# Voltage_Regulators.net
KiCad netlist of a schematic drawn in Altium Designer
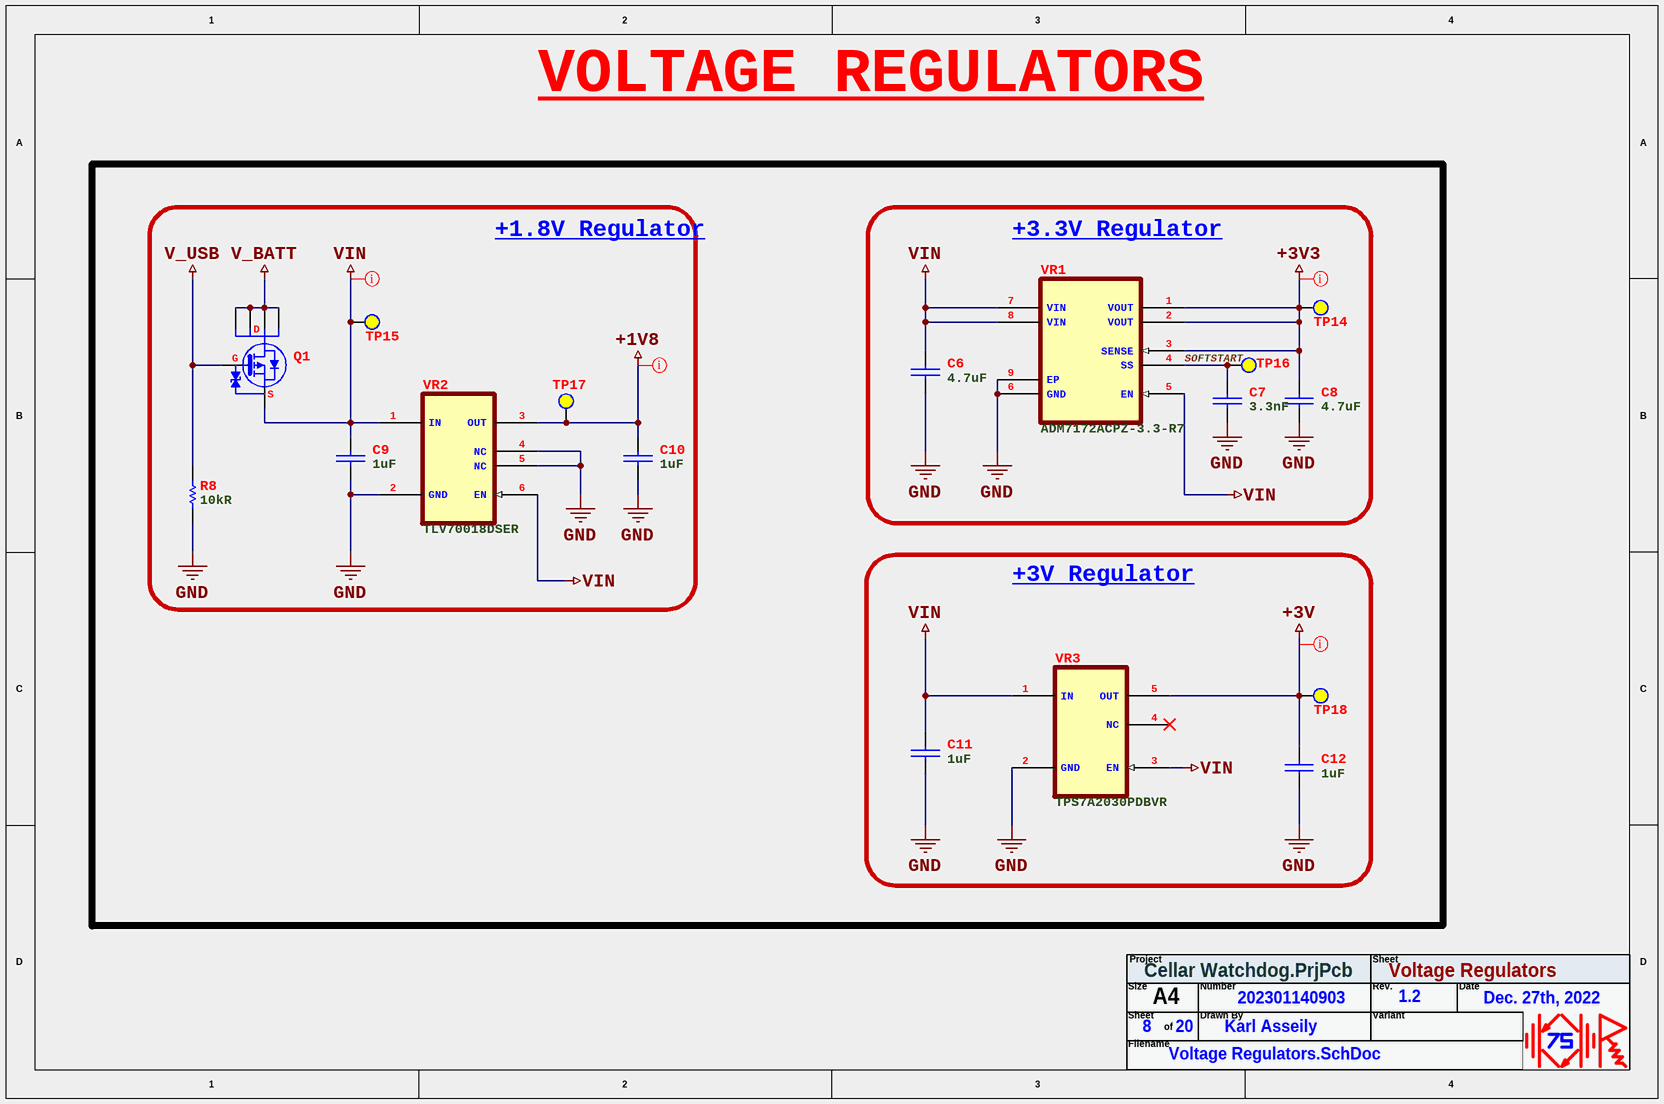
[diagram p0: Voltage Regulators.SchDoc]

(export (version "E")
  (design (tool "Eeschema 10.0.6"))
  (components
    (comp (ref "C6")
      (value "4.7uF")
      (footprint "CAP_0805")
      (description "4.7 µF ±10% 25V Ceramic Capacitor X7R 0805 (2012 Metric)")
      (fields
        (field (name "MANUFACTURER") "Yageo")
        (field (name "MANUFACTURER PART NUMBER") "CC0805KKX7R8BB475")
      )
      (libsource (lib "Cellar Watchdog") (part "CAP_4.7uF-25V-10%_0805"))
    )
    (comp (ref "C7")
      (value "3.3nF")
      (footprint "CAP_0603")
      (description "3300 pF ±10% 50V Ceramic Capacitor X7R 0603 (1608 Metric)")
      (fields
        (field (name "MANUFACTURER") "Yageo")
        (field (name "MANUFACTURER PART NUMBER") "CC0603KRX7R9BB332")
      )
      (libsource (lib "Cellar Watchdog") (part "CAP_3.3nF-50V-10%_0603"))
    )
    (comp (ref "C8")
      (value "4.7uF")
      (footprint "CAP_0805")
      (description "4.7 µF ±10% 25V Ceramic Capacitor X7R 0805 (2012 Metric)")
      (fields
        (field (name "MANUFACTURER") "Yageo")
        (field (name "MANUFACTURER PART NUMBER") "CC0805KKX7R8BB475")
      )
      (libsource (lib "Cellar Watchdog") (part "CAP_4.7uF-25V-10%_0805"))
    )
    (comp (ref "C9")
      (value "1uF")
      (footprint "CAP_0805")
      (description "1 µF ±10% 16V Ceramic Capacitor X7R 0603 (1608 Metric)")
      (fields
        (field (name "MANUFACTURER") "Yageo")
        (field (name "MANUFACTURER PART NUMBER") "CC0603KRX7R7BB105")
      )
      (libsource (lib "Cellar Watchdog") (part "CAP_1uF-16V-10%_0603"))
    )
    (comp (ref "C10")
      (value "1uF")
      (footprint "CAP_0805")
      (description "1 µF ±10% 16V Ceramic Capacitor X7R 0603 (1608 Metric)")
      (fields
        (field (name "MANUFACTURER") "Yageo")
        (field (name "MANUFACTURER PART NUMBER") "CC0603KRX7R7BB105")
      )
      (libsource (lib "Cellar Watchdog") (part "CAP_1uF-16V-10%_0603"))
    )
    (comp (ref "C11")
      (value "1uF")
      (footprint "CAP_0805")
      (description "1 µF ±10% 16V Ceramic Capacitor X7R 0603 (1608 Metric)")
      (fields
        (field (name "MANUFACTURER") "Yageo")
        (field (name "MANUFACTURER PART NUMBER") "CC0603KRX7R7BB105")
      )
      (libsource (lib "Cellar Watchdog") (part "CAP_1uF-16V-10%_0603"))
    )
    (comp (ref "C12")
      (value "1uF")
      (footprint "CAP_0805")
      (description "1 µF ±10% 16V Ceramic Capacitor X7R 0603 (1608 Metric)")
      (fields
        (field (name "MANUFACTURER") "Yageo")
        (field (name "MANUFACTURER PART NUMBER") "CC0603KRX7R7BB105")
      )
      (libsource (lib "Cellar Watchdog") (part "CAP_1uF-16V-10%_0603"))
    )
    (comp (ref "Q1")
      (value "SSM6J412TU,LF")
      (footprint "MOS_SOTFL65P210X75-6N")
      (description "P-Channel 20 V 4A (Ta) 1W (Ta) Surface Mount UF6")
      (fields (field (name "MANUFACTURER") "Toshiba"))
      (libsource (lib "Cellar Watchdog") (part "MOS-P_20V-4A-42.7mR_6-UF"))
    )
    (comp (ref "R8")
      (value "10kR")
      (footprint "RES_0603")
      (description "10 kOhms ±1% 0.1W, 1/10W Chip Resistor 0603 (1608 Metric) Moisture Resistant Thick Film")
      (fields
        (field (name "MANUFACTURER") "Yageo")
        (field (name "MANUFACTURER PART NUMBER") "RC0603FR-0710KL")
      )
      (libsource (lib "Cellar Watchdog") (part "RES_10kR-100mW-1%_0603"))
    )
    (comp (ref "TP14")
      (value "+3V3")
      (footprint "TEST POINT PAD")
      (description "PCB Test Point")
      (libsource (lib "Cellar Watchdog") (part "Test Point"))
    )
    (comp (ref "TP15")
      (value "VIN")
      (footprint "TEST POINT PAD")
      (description "PCB Test Point")
      (libsource (lib "Cellar Watchdog") (part "Test Point"))
    )
    (comp (ref "TP16")
      (value "SOFTSTART")
      (footprint "TEST POINT HOLE")
      (description "PCB Test Point")
      (libsource (lib "Cellar Watchdog") (part "Test Point"))
    )
    (comp (ref "TP17")
      (value "+1V8")
      (footprint "TEST POINT PAD")
      (description "PCB Test Point")
      (libsource (lib "Cellar Watchdog") (part "Test Point"))
    )
    (comp (ref "TP18")
      (value "+3V")
      (footprint "TEST POINT PAD")
      (description "PCB Test Point")
      (libsource (lib "Cellar Watchdog") (part "Test Point"))
    )
    (comp (ref "VR1")
      (value "ADM7172ACPZ-3.3-R7")
      (footprint "REG_SON50P300X300X80-9N")
      (description "Linear Voltage Regulator IC Positive Fixed 1 Output 2A 8-LFCSP-WD (3x3)")
      (fields (field (name "MANUFACTURER") "Analog Devices"))
      (libsource (lib "Cellar Watchdog") (part "REG_3.3V-2A_8-LFCSP-WD"))
    )
    (comp (ref "VR2")
      (value "TLV70018DSER")
      (footprint "REG_SON50P150X150X80-6N")
      (description "Linear Voltage Regulator IC Positive Fixed 1 Output 200mA 6-WSON (1.5x1.5)")
      (fields (field (name "MANUFACTURER") "Texas Instruments"))
      (libsource (lib "Cellar Watchdog") (part "REG_1.8V-200mA_6-WSON"))
    )
    (comp (ref "VR3")
      (value "TPS7A2030PDBVR")
      (footprint "REG_SOT95P280X145-5N")
      (description "Linear Voltage Regulator IC Positive Fixed 1 Output 300mA SOT-23-5")
      (fields (field (name "MANUFACTURER") "Texas Instruments"))
      (libsource (lib "Cellar Watchdog") (part "REG_3V-300mA_SOT-23-5"))
    )
  )
  (nets
    (net (code "1") (name "+1V8") (class "Default")
      (node (ref "C10") (pin "1") (pinfunction "1_1") (pintype "passive"))
      (node (ref "TP17") (pin "TP") (pinfunction "TP_TP") (pintype "passive"))
      (node (ref "VR2") (pin "3") (pinfunction "OUT_3") (pintype "power_in"))
    )
    (net (code "2") (name "+3V") (class "Default")
      (node (ref "C12") (pin "1") (pinfunction "1_1") (pintype "passive"))
      (node (ref "TP18") (pin "TP") (pinfunction "TP_TP") (pintype "passive"))
      (node (ref "VR3") (pin "5") (pinfunction "OUT_5") (pintype "power_in"))
    )
    (net (code "3") (name "+3V3") (class "Default")
      (node (ref "C8") (pin "1") (pinfunction "1_1") (pintype "passive"))
      (node (ref "TP14") (pin "TP") (pinfunction "TP_TP") (pintype "passive"))
      (node (ref "VR1") (pin "1") (pinfunction "VOUT_1") (pintype "power_in"))
      (node (ref "VR1") (pin "2") (pinfunction "VOUT_2") (pintype "power_in"))
      (node (ref "VR1") (pin "3") (pinfunction "SENSE_3") (pintype "input"))
    )
    (net (code "4") (name "/SOFTSTART") (class "Default")
      (node (ref "C7") (pin "1") (pinfunction "1_1") (pintype "passive"))
      (node (ref "TP16") (pin "TP") (pinfunction "TP_TP") (pintype "passive"))
      (node (ref "VR1") (pin "4") (pinfunction "SS_4") (pintype "passive"))
    )
    (net (code "5") (name "GND") (class "Default")
      (node (ref "C10") (pin "2") (pinfunction "2_2") (pintype "passive"))
      (node (ref "C11") (pin "2") (pinfunction "2_2") (pintype "passive"))
      (node (ref "C12") (pin "2") (pinfunction "2_2") (pintype "passive"))
      (node (ref "C6") (pin "2") (pinfunction "2_2") (pintype "passive"))
      (node (ref "C7") (pin "2") (pinfunction "2_2") (pintype "passive"))
      (node (ref "C8") (pin "2") (pinfunction "2_2") (pintype "passive"))
      (node (ref "C9") (pin "2") (pinfunction "2_2") (pintype "passive"))
      (node (ref "R8") (pin "2") (pinfunction "2_2") (pintype "passive"))
      (node (ref "VR1") (pin "6") (pinfunction "GND_6") (pintype "power_in"))
      (node (ref "VR1") (pin "9") (pinfunction "EP_9") (pintype "power_in"))
      (node (ref "VR2") (pin "2") (pinfunction "GND_2") (pintype "power_in"))
      (node (ref "VR2") (pin "4") (pinfunction "NC_4") (pintype "passive"))
      (node (ref "VR2") (pin "5") (pinfunction "NC_5") (pintype "passive"))
      (node (ref "VR3") (pin "2") (pinfunction "GND_2") (pintype "power_in"))
    )
    (net (code "6") (name "VIN") (class "Default")
      (node (ref "C11") (pin "1") (pinfunction "1_1") (pintype "passive"))
      (node (ref "C6") (pin "1") (pinfunction "1_1") (pintype "passive"))
      (node (ref "C9") (pin "1") (pinfunction "1_1") (pintype "passive"))
      (node (ref "Q1") (pin "4") (pinfunction "S_4") (pintype "passive"))
      (node (ref "TP15") (pin "TP") (pinfunction "TP_TP") (pintype "passive"))
      (node (ref "VR1") (pin "5") (pinfunction "EN_5") (pintype "input"))
      (node (ref "VR1") (pin "7") (pinfunction "VIN_7") (pintype "power_in"))
      (node (ref "VR1") (pin "8") (pinfunction "VIN_8") (pintype "power_in"))
      (node (ref "VR2") (pin "1") (pinfunction "IN_1") (pintype "power_in"))
      (node (ref "VR2") (pin "6") (pinfunction "EN_6") (pintype "input"))
      (node (ref "VR3") (pin "1") (pinfunction "IN_1") (pintype "power_in"))
      (node (ref "VR3") (pin "3") (pinfunction "EN_3") (pintype "input"))
    )
    (net (code "7") (name "V_BATT") (class "Default")
      (node (ref "Q1") (pin "1") (pinfunction "D_1") (pintype "passive"))
      (node (ref "Q1") (pin "2") (pinfunction "D_2") (pintype "passive"))
      (node (ref "Q1") (pin "5") (pinfunction "D_5") (pintype "passive"))
      (node (ref "Q1") (pin "6") (pinfunction "D_6") (pintype "passive"))
    )
    (net (code "8") (name "V_USB") (class "Default")
      (node (ref "Q1") (pin "3") (pinfunction "G_3") (pintype "passive"))
      (node (ref "R8") (pin "1") (pinfunction "1_1") (pintype "passive"))
    )
    (net (code "9") (name "unconnected-(VR3-NC-Pad4)") (class "Default")
      (node (ref "VR3") (pin "4") (pinfunction "NC_4") (pintype "passive+no_connect"))
    )
  )
)
